# SumoBot.net
KiCad netlist of a schematic drawn in EAGLE
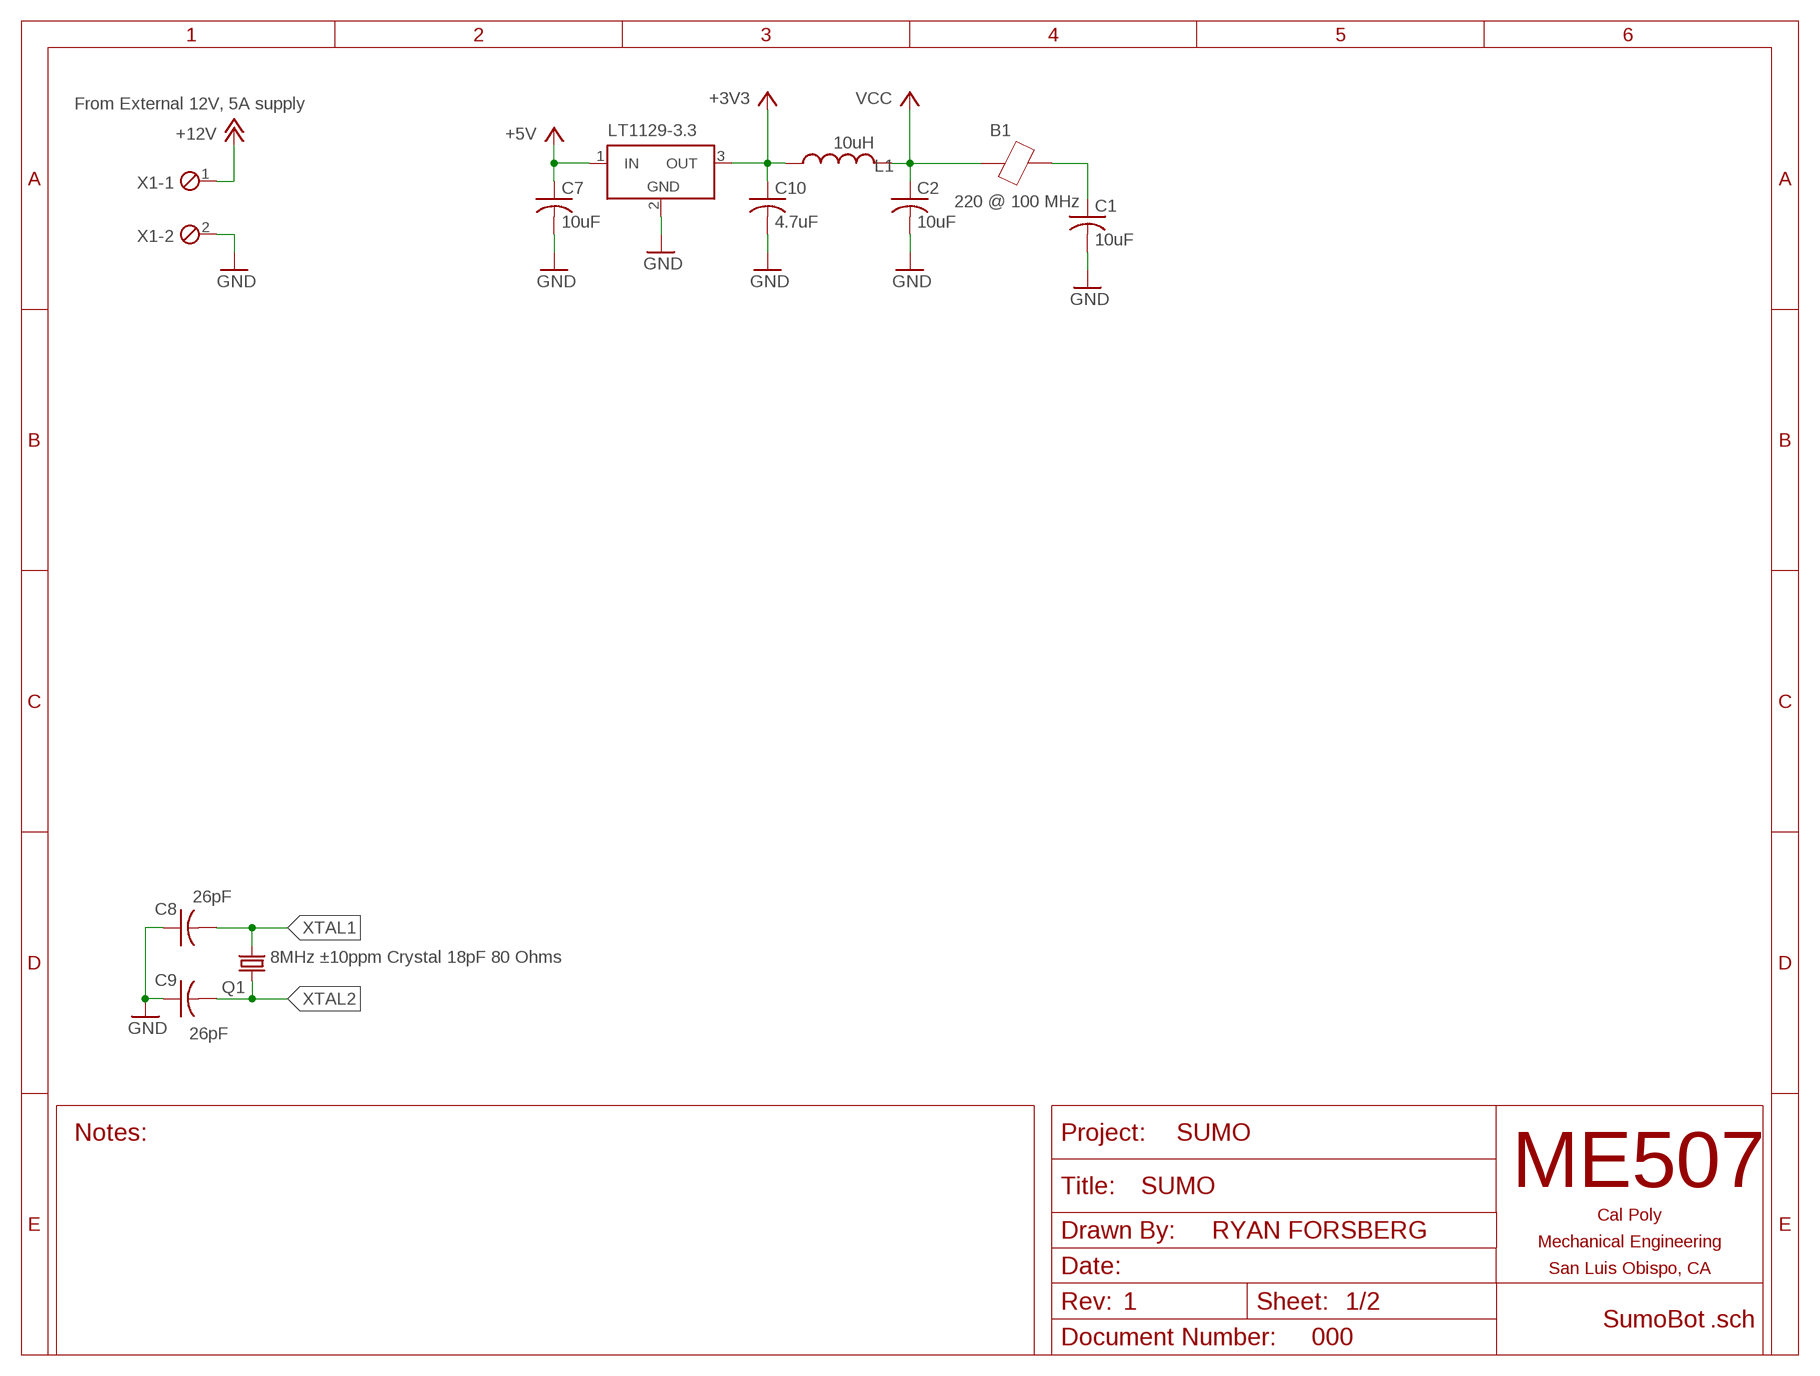
[diagram p0: schematic, sheet 1]
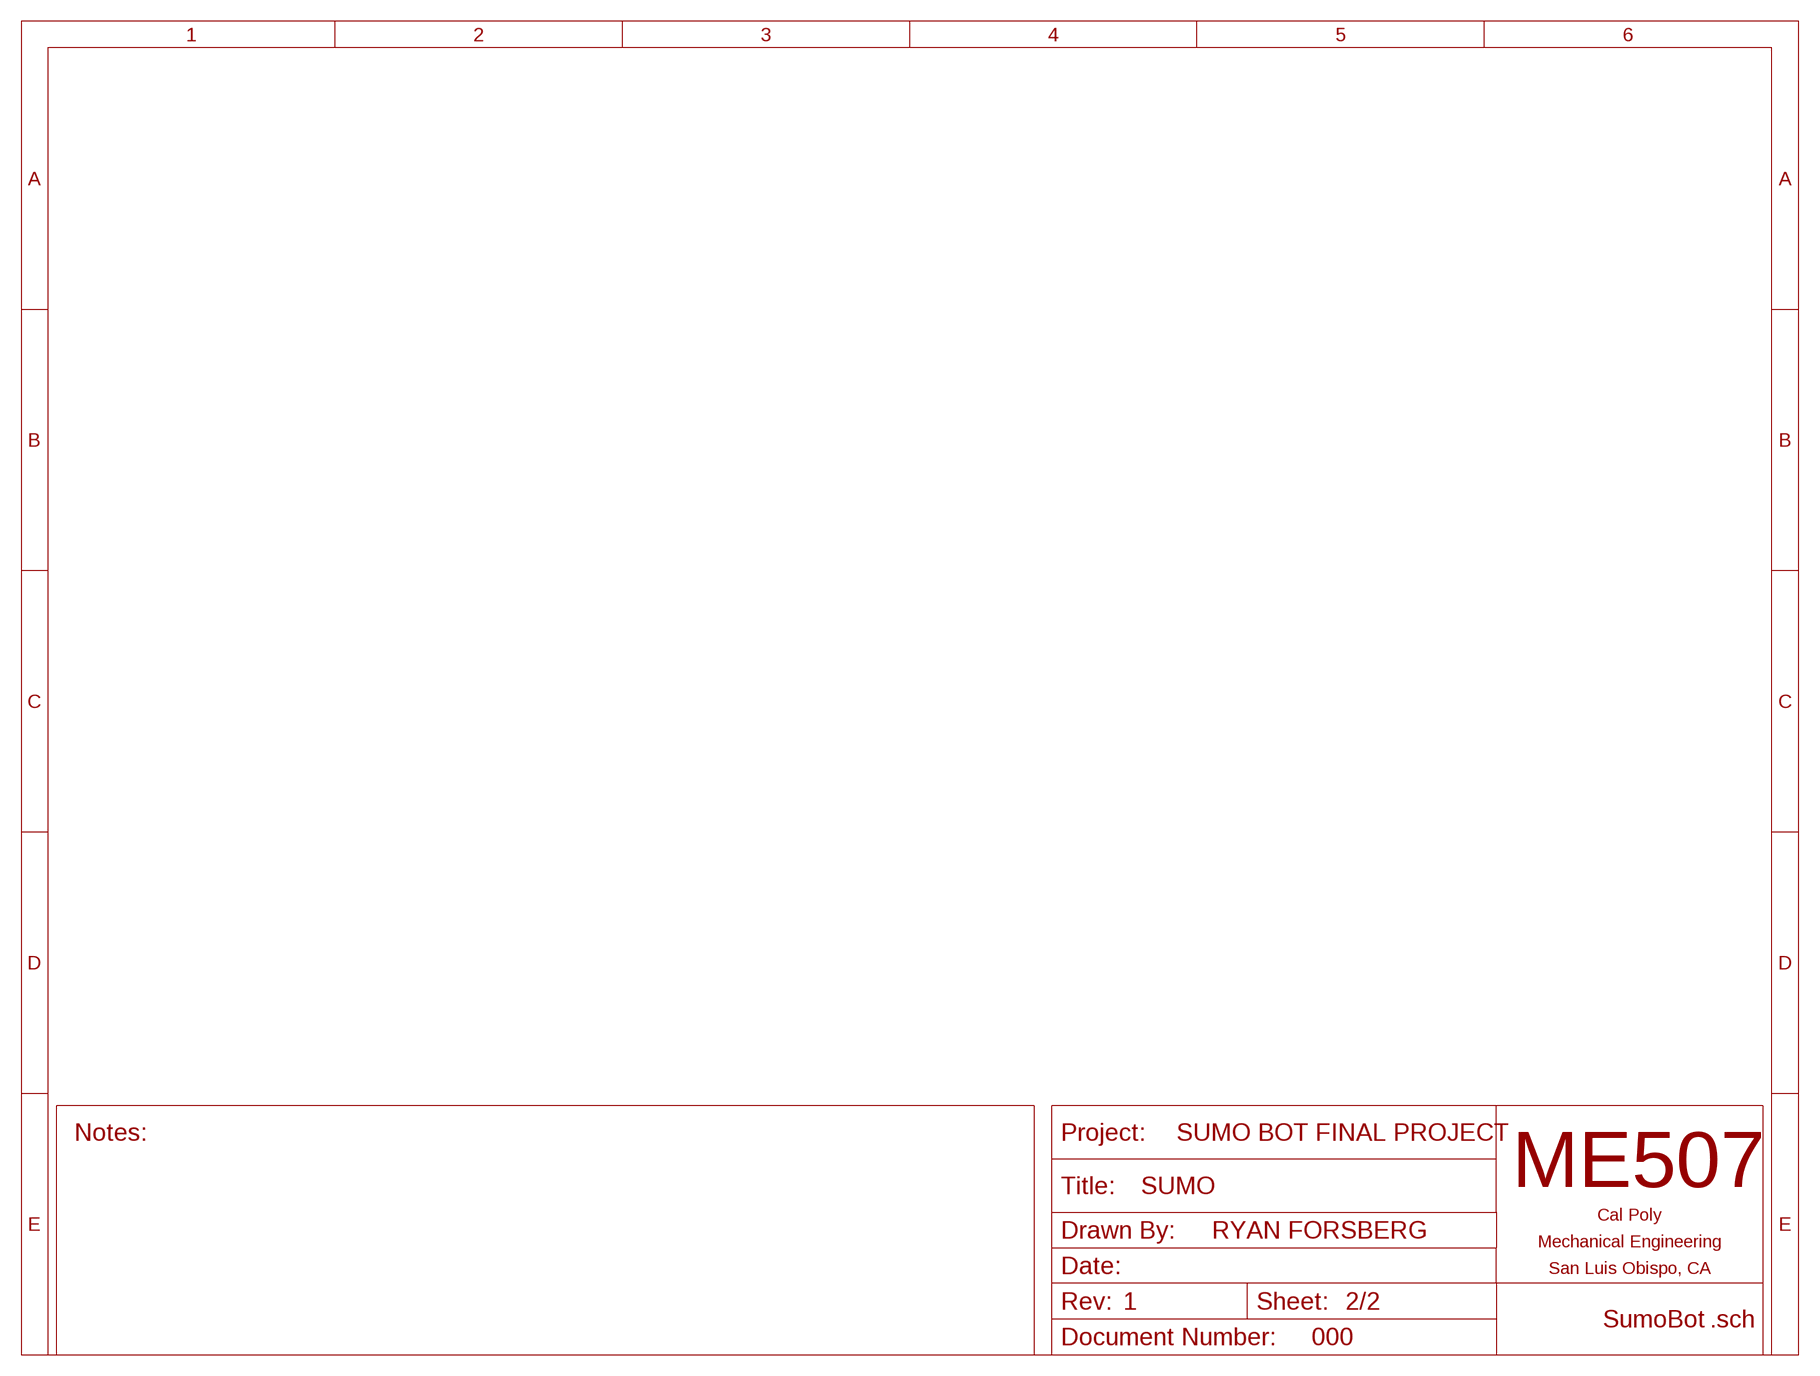
[diagram p1: schematic, sheet 2]

(export (version "E")
  (design (tool "Eeschema 10.0.6"))
  (components
    (comp (ref "B1")
      (value "220 @ 100 MHz")
      (footprint "eagle-import:1210")
      (libsource (lib "eagle-import") (part "BEAD1210"))
    )
    (comp (ref "C1")
      (value "10uF")
      (footprint "eagle-import:C0805")
      (libsource (lib "eagle-import") (part "C-USC0805"))
    )
    (comp (ref "C2")
      (value "10uF")
      (footprint "eagle-import:C0805")
      (libsource (lib "eagle-import") (part "C-USC0805"))
    )
    (comp (ref "C7")
      (value "10uF")
      (footprint "eagle-import:C0805")
      (libsource (lib "eagle-import") (part "C-USC0805"))
    )
    (comp (ref "C8")
      (value "26pF")
      (footprint "eagle-import:C0805")
      (libsource (lib "eagle-import") (part "C-USC0805"))
    )
    (comp (ref "C9")
      (value "26pF")
      (footprint "eagle-import:C0805")
      (libsource (lib "eagle-import") (part "C-USC0805"))
    )
    (comp (ref "C10")
      (value "4.7uF")
      (footprint "eagle-import:C0805")
      (libsource (lib "eagle-import") (part "C-USC0805"))
    )
    (comp (ref "L1")
      (value "10uH")
      (footprint "eagle-import:L3225M")
      (libsource (lib "eagle-import") (part "L-USL3225M"))
    )
    (comp (ref "LT1129-3.3")
      (value "LT1129CST5")
      (footprint "eagle-import:SOT223")
      (fields (field (name "MPN") "LT1129CST-5#PBF"))
      (libsource (lib "eagle-import") (part "LT1129CST5"))
    )
    (comp (ref "Q1")
      (value "8MHz ±10ppm Crystal 18pF 80 Ohms")
      (footprint "eagle-import:HC49UP")
      (libsource (lib "eagle-import") (part "CRYSTALHC49UP"))
    )
    (comp (ref "X1")
      (value "SCREWTERM_2P_381")
      (footprint "eagle-import:2POL381")
      (libsource (lib "eagle-import") (part "SCREWTERM_2P_381"))
    )
  )
  (nets
    (net (code "1") (name "+3V3") (class "Default")
      (node (ref "C10") (pin "1") (pinfunction "1_1") (pintype "passive"))
      (node (ref "L1") (pin "1") (pinfunction "1_1") (pintype "passive"))
      (node (ref "LT1129-3.3") (pin "3") (pinfunction "OUT_3") (pintype "output"))
    )
    (net (code "2") (name "+5V") (class "Default")
      (node (ref "C7") (pin "1") (pinfunction "1_1") (pintype "passive"))
      (node (ref "LT1129-3.3") (pin "1") (pinfunction "IN_1") (pintype "input"))
    )
    (net (code "3") (name "+12V") (class "Default")
      (node (ref "X1") (pin "1") (pinfunction "1_1") (pintype "passive"))
    )
    (net (code "4") (name "GND") (class "Default")
      (node (ref "C1") (pin "2") (pinfunction "2_2") (pintype "passive"))
      (node (ref "C10") (pin "2") (pinfunction "2_2") (pintype "passive"))
      (node (ref "C2") (pin "2") (pinfunction "2_2") (pintype "passive"))
      (node (ref "C7") (pin "2") (pinfunction "2_2") (pintype "passive"))
      (node (ref "C8") (pin "1") (pinfunction "1_1") (pintype "passive"))
      (node (ref "C9") (pin "1") (pinfunction "1_1") (pintype "passive"))
      (node (ref "LT1129-3.3") (pin "2") (pinfunction "GND_2") (pintype "power_in"))
      (node (ref "X1") (pin "2") (pinfunction "1_2") (pintype "passive"))
    )
    (net (code "5") (name "Net-(B1-Pad2)") (class "Default")
      (node (ref "B1") (pin "2") (pinfunction "2_2") (pintype "bidirectional"))
      (node (ref "C1") (pin "1") (pinfunction "1_1") (pintype "passive"))
    )
    (net (code "6") (name "VCC") (class "Default")
      (node (ref "B1") (pin "1") (pinfunction "1_1") (pintype "bidirectional"))
      (node (ref "C2") (pin "1") (pinfunction "1_1") (pintype "passive"))
      (node (ref "L1") (pin "2") (pinfunction "2_2") (pintype "passive"))
    )
    (net (code "7") (name "XTAL1") (class "Default")
      (node (ref "C8") (pin "2") (pinfunction "2_2") (pintype "passive"))
      (node (ref "Q1") (pin "2") (pinfunction "2_2") (pintype "passive"))
    )
    (net (code "8") (name "XTAL2") (class "Default")
      (node (ref "C9") (pin "2") (pinfunction "2_2") (pintype "passive"))
      (node (ref "Q1") (pin "1") (pinfunction "1_1") (pintype "passive"))
    )
  )
)
